# ADC_Soldier.net
KiCad netlist of a schematic drawn in Altium Designer
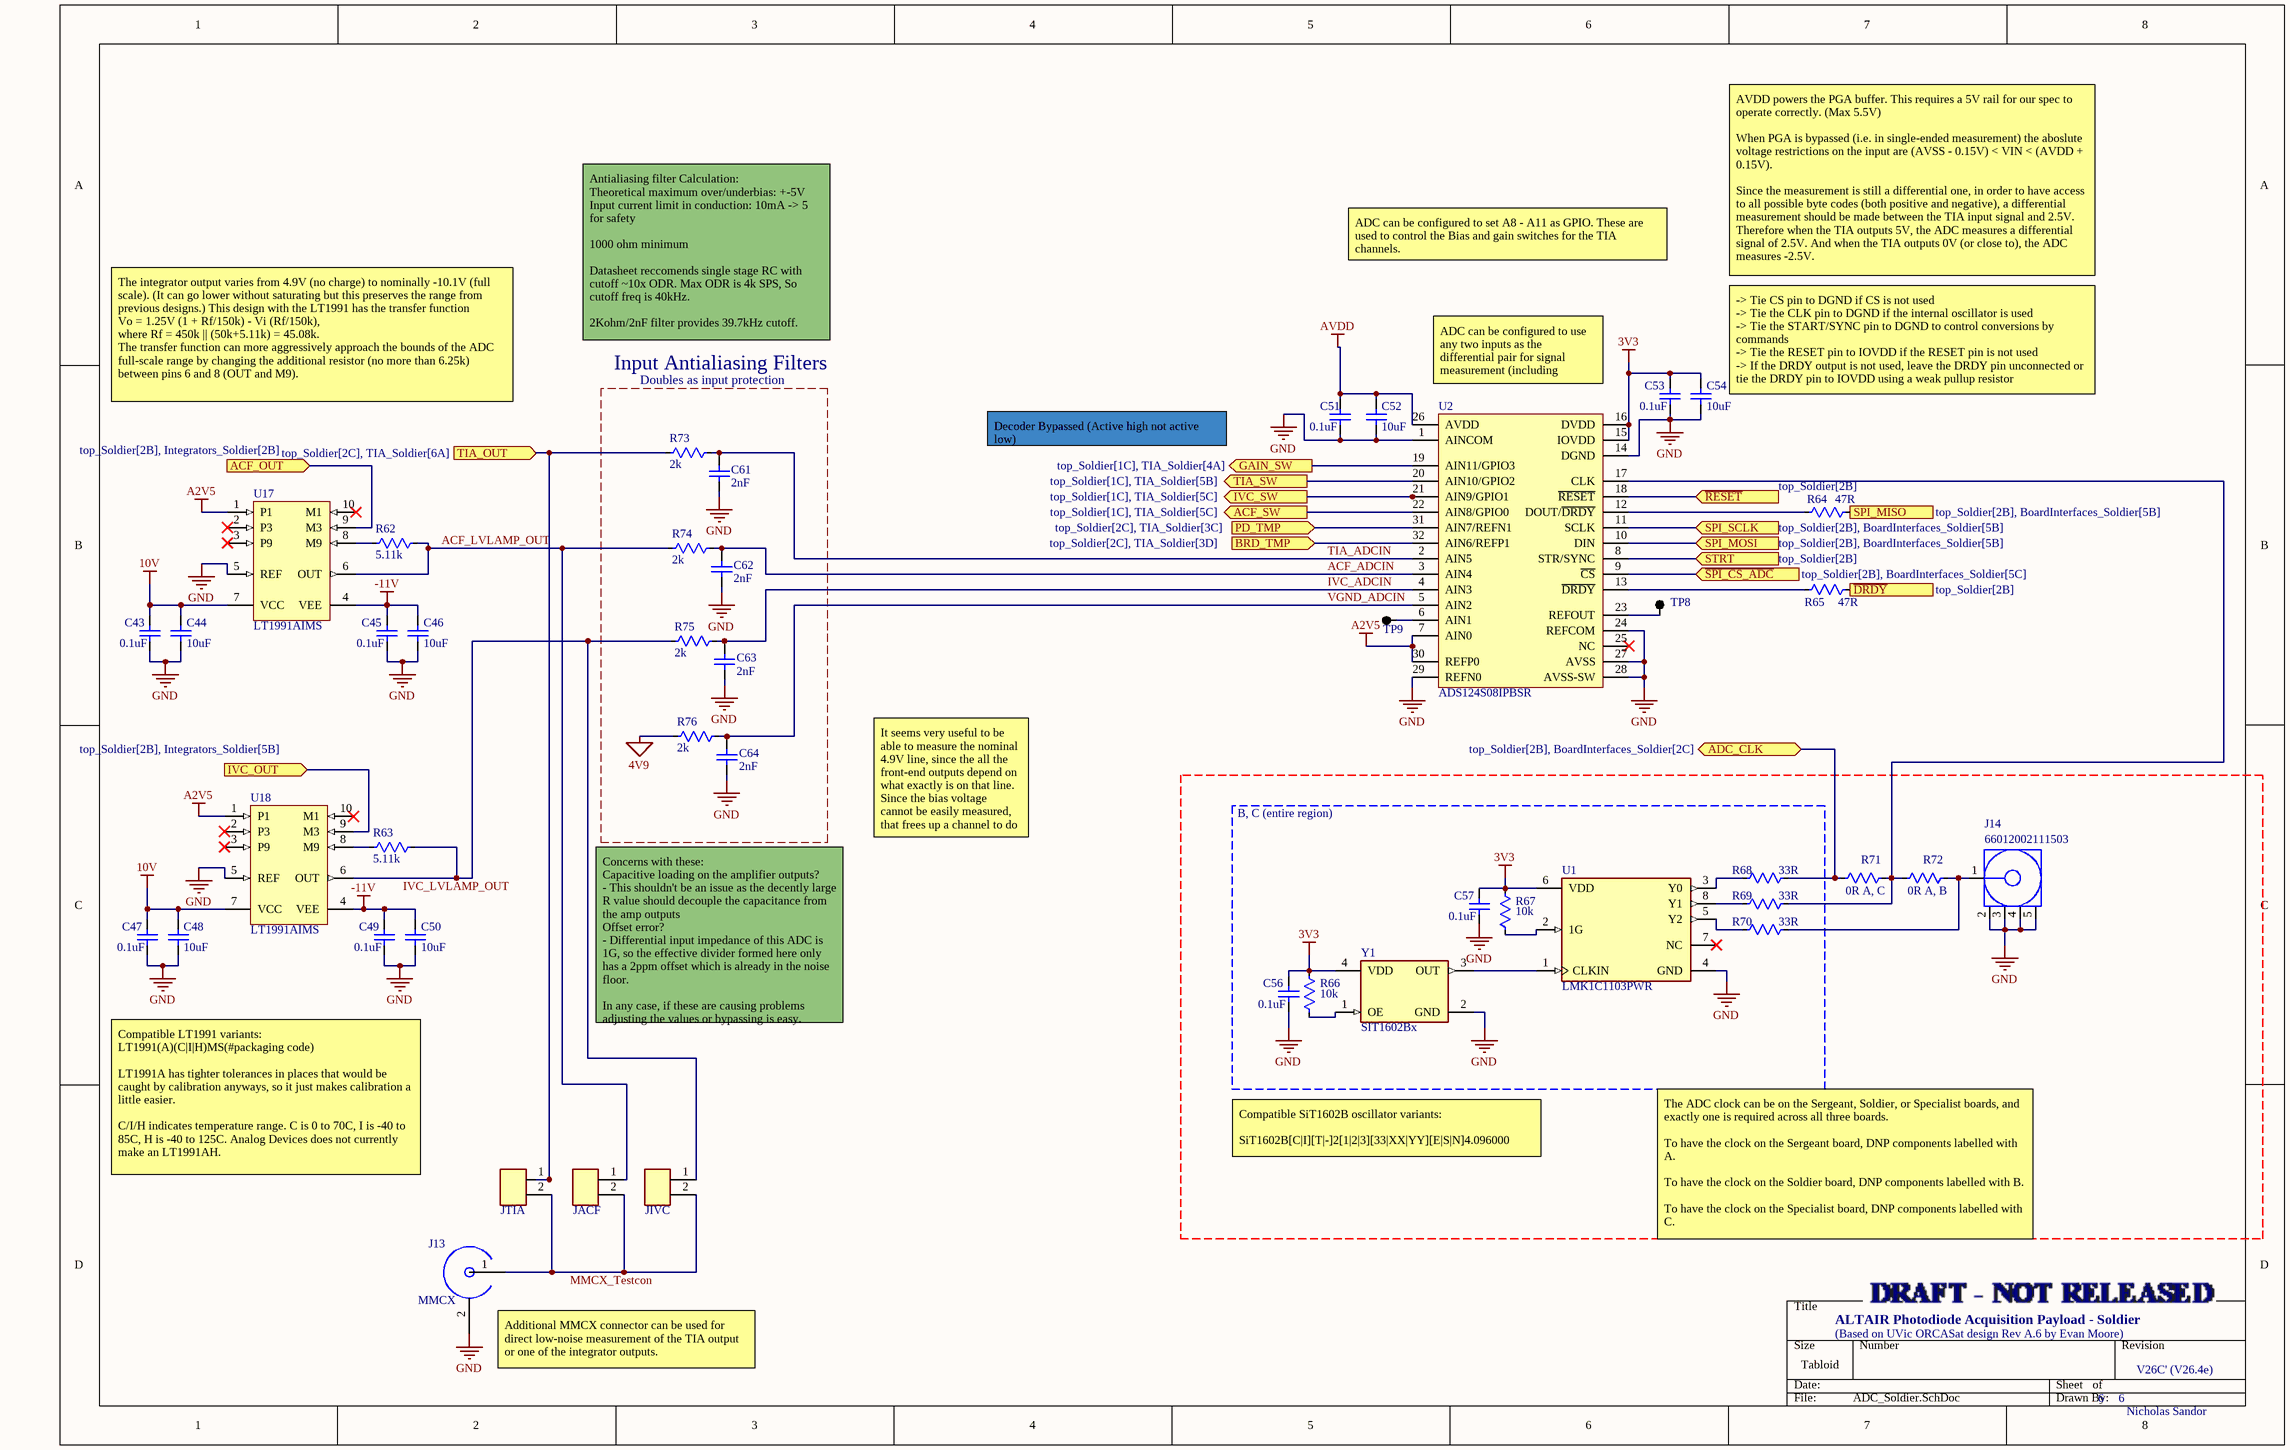
[diagram p0: ADC_Soldier.SchDoc]

(export (version "E")
  (design (tool "Eeschema 10.0.6"))
  (components
    (comp (ref "C43")
      (value "0.1uF")
      (footprint "CAP 0603 NON-IPC KEMET X7R")
      (description "Kemet C0603C104K5RACAUTO - Cap Ceramic 0.1uF 50V X7R 10% 0603 125C Paper T/R")
      (fields (field (name "MF") "Kemet") (field (name "MP") "C0603C104K5RACAUTO"))
      (libsource (lib "ALTAIR_PD_Capacitors") (part "CAP"))
    )
    (comp (ref "C44")
      (value "10uF")
      (footprint "CAP 0805 IPC MID DENSITY")
      (description "Murata GRM21BR61E106KA73L - Cap Ceramic 10uF 10% 25V X5R 0805")
      (fields (field (name "MF") "Murata") (field (name "MP") "GRM21BR61E106KA73L"))
      (libsource (lib "ALTAIR_PD_Capacitors") (part "CAP"))
    )
    (comp (ref "C45")
      (value "0.1uF")
      (footprint "CAP 0603 NON-IPC KEMET X7R")
      (description "Kemet C0603C104K5RACAUTO - Cap Ceramic 0.1uF 50V X7R 10% 0603 125C Paper T/R")
      (fields (field (name "MF") "Kemet") (field (name "MP") "C0603C104K5RACAUTO"))
      (libsource (lib "ALTAIR_PD_Capacitors") (part "CAP"))
    )
    (comp (ref "C46")
      (value "10uF")
      (footprint "CAP 0805 IPC MID DENSITY")
      (description "Murata GRM21BR61E106KA73L - Cap Ceramic 10uF 10% 25V X5R 0805")
      (fields (field (name "MF") "Murata") (field (name "MP") "GRM21BR61E106KA73L"))
      (libsource (lib "ALTAIR_PD_Capacitors") (part "CAP"))
    )
    (comp (ref "C47")
      (value "0.1uF")
      (footprint "CAP 0603 NON-IPC KEMET X7R")
      (description "Kemet C0603C104K5RACAUTO - Cap Ceramic 0.1uF 50V X7R 10% 0603 125C Paper T/R")
      (fields (field (name "MF") "Kemet") (field (name "MP") "C0603C104K5RACAUTO"))
      (libsource (lib "ALTAIR_PD_Capacitors") (part "CAP"))
    )
    (comp (ref "C48")
      (value "10uF")
      (footprint "CAP 0805 IPC MID DENSITY")
      (description "Murata GRM21BR61E106KA73L - Cap Ceramic 10uF 10% 25V X5R 0805")
      (fields (field (name "MF") "Murata") (field (name "MP") "GRM21BR61E106KA73L"))
      (libsource (lib "ALTAIR_PD_Capacitors") (part "CAP"))
    )
    (comp (ref "C49")
      (value "0.1uF")
      (footprint "CAP 0603 NON-IPC KEMET X7R")
      (description "Kemet C0603C104K5RACAUTO - Cap Ceramic 0.1uF 50V X7R 10% 0603 125C Paper T/R")
      (fields (field (name "MF") "Kemet") (field (name "MP") "C0603C104K5RACAUTO"))
      (libsource (lib "ALTAIR_PD_Capacitors") (part "CAP"))
    )
    (comp (ref "C50")
      (value "10uF")
      (footprint "CAP 0805 IPC MID DENSITY")
      (description "Murata GRM21BR61E106KA73L - Cap Ceramic 10uF 10% 25V X5R 0805")
      (fields (field (name "MF") "Murata") (field (name "MP") "GRM21BR61E106KA73L"))
      (libsource (lib "ALTAIR_PD_Capacitors") (part "CAP"))
    )
    (comp (ref "C51")
      (value "0.1uF")
      (footprint "CAP 0603 IPC MID DENSITY")
      (description "Kemet C0603C104K5RACAUTO - Cap Ceramic 0.1uF 50V X7R 10% 0603 125C Paper T/R")
      (fields (field (name "MF") "Kemet") (field (name "MP") "C0603C104K5RACAUTO"))
      (libsource (lib "ALTAIR_PD_Capacitors") (part "CAP"))
    )
    (comp (ref "C52")
      (value "10uF")
      (footprint "CAP 0805 IPC MID DENSITY")
      (description "Murata GRM21BR61E106KA73L - Cap Ceramic 10uF 10% 25V X5R 0805")
      (fields (field (name "MF") "Murata") (field (name "MP") "GRM21BR61E106KA73L"))
      (libsource (lib "ALTAIR_PD_Capacitors") (part "CAP"))
    )
    (comp (ref "C53")
      (value "0.1uF")
      (footprint "CAP 0603 IPC MID DENSITY")
      (description "Kemet C0603C104K5RACAUTO - Cap Ceramic 0.1uF 50V X7R 10% 0603 125C Paper T/R")
      (fields (field (name "MF") "Kemet") (field (name "MP") "C0603C104K5RACAUTO"))
      (libsource (lib "ALTAIR_PD_Capacitors") (part "CAP"))
    )
    (comp (ref "C54")
      (value "10uF")
      (footprint "CAP 0805 IPC MID DENSITY")
      (description "Murata GRM21BR61E106KA73L - Cap Ceramic 10uF 10% 25V X5R 0805")
      (fields (field (name "MF") "Murata") (field (name "MP") "GRM21BR61E106KA73L"))
      (libsource (lib "ALTAIR_PD_Capacitors") (part "CAP"))
    )
    (comp (ref "C56")
      (value "0.1uF")
      (footprint "CAP 0603 IPC MID DENSITY")
      (description "Kemet C0603C104K5RACAUTO - Cap Ceramic 0.1uF 50V X7R 10% 0603 125C Paper T/R")
      (fields (field (name "MF") "Kemet") (field (name "MP") "C0603C104K5RACAUTO"))
      (libsource (lib "ALTAIR_PD_Capacitors") (part "CAP"))
    )
    (comp (ref "C57")
      (value "0.1uF")
      (footprint "CAP 0603 IPC MID DENSITY")
      (description "Kemet C0603C104K5RACAUTO - Cap Ceramic 0.1uF 50V X7R 10% 0603 125C Paper T/R")
      (fields (field (name "MF") "Kemet") (field (name "MP") "C0603C104K5RACAUTO"))
      (libsource (lib "ALTAIR_PD_Capacitors") (part "CAP"))
    )
    (comp (ref "C61")
      (value "2nF")
      (footprint "CAP 0603 IPC MID DENSITY")
      (description "Cap, Nonpolar, Any, Must choose footprint manually")
      (libsource (lib "ALTAIR_PD_Capacitors") (part "CAP"))
    )
    (comp (ref "C62")
      (value "2nF")
      (footprint "CAP 0603 IPC MID DENSITY")
      (description "Cap, Nonpolar, Any, Must choose footprint manually")
      (libsource (lib "ALTAIR_PD_Capacitors") (part "CAP"))
    )
    (comp (ref "C63")
      (value "2nF")
      (footprint "CAP 0603 IPC MID DENSITY")
      (description "Cap, Nonpolar, Any, Must choose footprint manually")
      (libsource (lib "ALTAIR_PD_Capacitors") (part "CAP"))
    )
    (comp (ref "C64")
      (value "2nF")
      (footprint "CAP 0603 IPC MID DENSITY")
      (description "Cap, Nonpolar, Any, Must choose footprint manually")
      (libsource (lib "ALTAIR_PD_Capacitors") (part "CAP"))
    )
    (comp (ref "J13")
      (value "MMCX")
      (footprint "COAX MMCX SMD")
      (description "Conn MMCX F 50Ohm Solder ST SMD Gold Tray")
      (fields (field (name "MF") "Molex") (field (name "MP") "0734152061"))
      (libsource (lib "ALTAIR_PD_Coaxial") (part "MMCX_recp"))
    )
    (comp (ref "J14")
      (value "66012002111503")
      (footprint "COAX MMCX THT")
      (description "Rf Coaxial, Mmcx Jack, 50 Ohm, Pcb Rohs Compliant: Yes ¦Wurth Elektronik 66012002111503")
      (fields (field (name "MF") "Wurth Elektronik"))
      (libsource (lib "ALTAIR_PD_Coaxial") (part "CMP-207975-000001-3"))
    )
    (comp (ref "JACF")
      (value "JACF")
      (footprint "ALTAIR_PD_Headers:JUMPER 2POS 1MM PITCH THT")
      (description "2x1 Header THT 1mm Pitch")
      (fields
        (field (name "MF") "GCT (GLOBAL CONNECTOR TECHNOLOGY)")
        (field (name "MP") "BC020-02-A-0200-0300-L-G")
      )
      (libsource (lib "ALTAIR_PD_Headers") (part "BC020-02-A-0200-0300-L-G"))
    )
    (comp (ref "JIVC")
      (value "JIVC")
      (footprint "ALTAIR_PD_Headers:JUMPER 2POS 1MM PITCH THT")
      (description "2x1 Header THT 1mm Pitch")
      (fields
        (field (name "MF") "GCT (GLOBAL CONNECTOR TECHNOLOGY)")
        (field (name "MP") "BC020-02-A-0200-0300-L-G")
      )
      (libsource (lib "ALTAIR_PD_Headers") (part "BC020-02-A-0200-0300-L-G"))
    )
    (comp (ref "JTIA")
      (value "JTIA")
      (footprint "ALTAIR_PD_Headers:JUMPER 2POS 1MM PITCH THT")
      (description "2x1 Header THT 1mm Pitch")
      (fields
        (field (name "MF") "GCT (GLOBAL CONNECTOR TECHNOLOGY)")
        (field (name "MP") "BC020-02-A-0200-0300-L-G")
      )
      (libsource (lib "ALTAIR_PD_Headers") (part "BC020-02-A-0200-0300-L-G"))
    )
    (comp (ref "R62")
      (value "5.11k")
      (footprint "RES 0402 IPC MID DENSITY")
      (description "Panasonic ERA-2AEB5111X - Res 5.11k 0.1% 1/16W SMD 0402")
      (fields (field (name "MF") "Panasonic Electronic Components") (field (name "MP") "ERA-2AEB5111X"))
      (libsource (lib "ALTAIR_PD_Resistors") (part "RES"))
    )
    (comp (ref "R63")
      (value "5.11k")
      (footprint "RES 0402 IPC MID DENSITY")
      (description "Panasonic ERA-2AEB5111X - Res 5.11k 0.1% 1/16W SMD 0402")
      (fields (field (name "MF") "Panasonic Electronic Components") (field (name "MP") "ERA-2AEB5111X"))
      (libsource (lib "ALTAIR_PD_Resistors") (part "RES"))
    )
    (comp (ref "R64")
      (value "47R")
      (footprint "RES 0402 NON-IPC SEI")
      (description "Stackpole RMCF0402JT47R0 - Res 47Ohm 5% 0.063W 0402 Thick Film AEC-Q200 compliant")
      (fields (field (name "MF") "Stackpole Electronics Inc.") (field (name "MP") "RMCF0402JT47R0"))
      (libsource (lib "ALTAIR_PD_Resistors") (part "RES"))
    )
    (comp (ref "R65")
      (value "47R")
      (footprint "RES 0402 NON-IPC SEI")
      (description "Stackpole RMCF0402JT47R0 - Res 47Ohm 5% 0.063W 0402 Thick Film AEC-Q200 compliant")
      (fields (field (name "MF") "Stackpole Electronics Inc.") (field (name "MP") "RMCF0402JT47R0"))
      (libsource (lib "ALTAIR_PD_Resistors") (part "RES"))
    )
    (comp (ref "R66")
      (value "10k")
      (footprint "RES 0603 IPC MID DENSITY")
      (description "Vishay CRCW060310K0FKEA SMD 0603 10k, CRCW e3 Series, 75V, thick film, 100mW")
      (fields (field (name "MF") "Vishay Dale") (field (name "MP") "CRCW060310K0FKEA"))
      (libsource (lib "ALTAIR_PD_Resistors") (part "RES"))
    )
    (comp (ref "R67")
      (value "10k")
      (footprint "RES 0603 IPC MID DENSITY")
      (description "Vishay CRCW060310K0FKEA SMD 0603 10k, CRCW e3 Series, 75V, thick film, 100mW")
      (fields (field (name "MF") "Vishay Dale") (field (name "MP") "CRCW060310K0FKEA"))
      (libsource (lib "ALTAIR_PD_Resistors") (part "RES"))
    )
    (comp (ref "R68")
      (value "33R")
      (footprint "RES 0402 NON-IPC YAGEO")
      (description "Yageo RC0402FR-0733RL - Res 33Ohm 1% 1/16W 0402")
      (fields (field (name "MF") "YAGEO") (field (name "MP") "RC0402FR-0733RL"))
      (libsource (lib "ALTAIR_PD_Resistors") (part "RES"))
    )
    (comp (ref "R69")
      (value "33R")
      (footprint "RES 0402 NON-IPC YAGEO")
      (description "Yageo RC0402FR-0733RL - Res 33Ohm 1% 1/16W 0402")
      (fields (field (name "MF") "YAGEO") (field (name "MP") "RC0402FR-0733RL"))
      (libsource (lib "ALTAIR_PD_Resistors") (part "RES"))
    )
    (comp (ref "R70")
      (value "33R")
      (footprint "RES 0402 NON-IPC YAGEO")
      (description "Yageo RC0402FR-0733RL - Res 33Ohm 1% 1/16W 0402")
      (fields (field (name "MF") "YAGEO") (field (name "MP") "RC0402FR-0733RL"))
      (libsource (lib "ALTAIR_PD_Resistors") (part "RES"))
    )
    (comp (ref "R71")
      (value "0R A, C")
      (footprint "RES 0402 IPC MID DENSITY")
      (description "Yageo RC0402JR-070RL - Res 0 Ohms 1/16W SMD 0402")
      (fields (field (name "MF") "YAGEO") (field (name "MP") "RC0402JR-070RL"))
      (libsource (lib "ALTAIR_PD_Resistors") (part "RES"))
    )
    (comp (ref "R72")
      (value "0R A, B")
      (footprint "RES 0402 IPC MID DENSITY")
      (description "Yageo RC0402JR-070RL - Res 0 Ohms 1/16W SMD 0402")
      (fields (field (name "MF") "YAGEO") (field (name "MP") "RC0402JR-070RL"))
      (libsource (lib "ALTAIR_PD_Resistors") (part "RES"))
    )
    (comp (ref "R73")
      (value "2k")
      (footprint "RES 0603 IPC MID DENSITY")
      (description "Res, Any, Manually select footprint")
      (libsource (lib "ALTAIR_PD_Resistors") (part "RES"))
    )
    (comp (ref "R74")
      (value "2k")
      (footprint "RES 0603 IPC MID DENSITY")
      (description "Res, Any, Manually select footprint")
      (libsource (lib "ALTAIR_PD_Resistors") (part "RES"))
    )
    (comp (ref "R75")
      (value "2k")
      (footprint "RES 0603 IPC MID DENSITY")
      (description "Res, Any, Manually select footprint")
      (libsource (lib "ALTAIR_PD_Resistors") (part "RES"))
    )
    (comp (ref "R76")
      (value "2k")
      (footprint "RES 0603 IPC MID DENSITY")
      (description "Res, Any, Manually select footprint")
      (libsource (lib "ALTAIR_PD_Resistors") (part "RES"))
    )
    (comp (ref "TP8")
      (value "Testpoint")
      (footprint "TESTPOINT THT")
      (libsource (lib "ALTAIR_PD_Testpoint") (part "Testpoint"))
    )
    (comp (ref "TP9")
      (value "Testpoint")
      (footprint "TESTPOINT THT")
      (libsource (lib "ALTAIR_PD_Testpoint") (part "Testpoint"))
    )
    (comp (ref "U1")
      (value "LMK1C1103PWR")
      (footprint "8-TSSOP 0.65MM PITCH 4.4MM WIDTH IPC MID DENSITY")
      (description "LVCMOS CLOCK BUFFER 3-CHANNEL")
      (fields (field (name "MF") "Texas Instruments"))
      (libsource (lib "ALTAIR_PD_ClockParts") (part "LMK1C1103PWR"))
    )
    (comp (ref "U2")
      (value "ADS124S08IPBSR")
      (footprint "32TQFP 7X7MM IPC LOW DENSITY")
      (description "24BIT ADC Delta-Sigma 4k samples/s PGA V-reference")
      (fields (field (name "MF") "Texas Instruments"))
      (libsource (lib "ALTAIR_PD_ADCs") (part "ADS124S08IPBSR"))
    )
    (comp (ref "U17")
      (value "LT1991AIMS")
      (footprint "10-SOP 0.5MM PITCH 3MM WIDTH IPC HIGH DENSITY")
      (fields
        (field (name "MF") "Linear Technology")
        (field (name "MP") "LT1991AIMS#PBF")
        (field (name "LINEAR TECHNOLOGY PART NUMBER") "LT1991")
      )
      (libsource (lib "ALTAIR_PD_Amplifiers") (part "LT1991IMS#TRPBF"))
    )
    (comp (ref "U18")
      (value "LT1991AIMS")
      (footprint "10-SOP 0.5MM PITCH 3MM WIDTH IPC HIGH DENSITY")
      (fields
        (field (name "MF") "Linear Technology")
        (field (name "MP") "LT1991AIMS#PBF")
        (field (name "LINEAR TECHNOLOGY PART NUMBER") "LT1991")
      )
      (libsource (lib "ALTAIR_PD_Amplifiers") (part "LT1991IMS#TRPBF"))
    )
    (comp (ref "Y1")
      (value "SIT1602Bx")
      (footprint "4PQFN NON-IPC SITIME")
      (description "MEMS OSC XO 4.096MHZ H/LVCMOS")
      (fields (field (name "MF") "SiTime") (field (name "MP") "SiT1602BC-21-XXN-4.096000"))
      (libsource (lib "ALTAIR_PD_ClockParts") (part "SIT1602Bx"))
    )
  )
  (nets
    (net (code "1") (name "-11V") (class "Default")
      (node (ref "C45") (pin "2") (pinfunction "2_2") (pintype "passive"))
      (node (ref "C46") (pin "2") (pinfunction "2_2") (pintype "passive"))
      (node (ref "C49") (pin "2") (pinfunction "2_2") (pintype "passive"))
      (node (ref "C50") (pin "2") (pinfunction "2_2") (pintype "passive"))
      (node (ref "U17") (pin "4") (pinfunction "VEE_4") (pintype "power_in"))
      (node (ref "U18") (pin "4") (pinfunction "VEE_4") (pintype "power_in"))
    )
    (net (code "2") (name "/ACF_ADCIN") (class "Default")
      (node (ref "C62") (pin "2") (pinfunction "2_2") (pintype "passive"))
      (node (ref "R74") (pin "2") (pinfunction "2_2") (pintype "passive"))
      (node (ref "U2") (pin "3") (pinfunction "AIN4_3") (pintype "passive"))
    )
    (net (code "3") (name "/ACF_LVLAMP_OUT") (class "Default")
      (node (ref "JACF") (pin "1") (pinfunction "1_1") (pintype "passive"))
      (node (ref "R62") (pin "2") (pinfunction "2_2") (pintype "passive"))
      (node (ref "R74") (pin "1") (pinfunction "1_1") (pintype "passive"))
      (node (ref "U17") (pin "6") (pinfunction "OUT_6") (pintype "output"))
    )
    (net (code "4") (name "/ACF_OUT") (class "Default")
      (node (ref "U17") (pin "9") (pinfunction "M3_9") (pintype "input"))
    )
    (net (code "5") (name "/ACF_SW") (class "Default")
      (node (ref "U2") (pin "22") (pinfunction "AIN8/GPIO0_22") (pintype "passive"))
    )
    (net (code "6") (name "/ADC_CLK") (class "Default")
      (node (ref "R68") (pin "1") (pinfunction "1_1") (pintype "passive"))
      (node (ref "R71") (pin "2") (pinfunction "2_2") (pintype "passive"))
    )
    (net (code "7") (name "/BRD_TMP") (class "Default")
      (node (ref "U2") (pin "32") (pinfunction "AIN6/REFP1_32") (pintype "passive"))
    )
    (net (code "8") (name "/DRDY") (class "Default")
      (node (ref "R65") (pin "2") (pinfunction "2_2") (pintype "passive"))
    )
    (net (code "9") (name "/GAIN_SW") (class "Default")
      (node (ref "U2") (pin "19") (pinfunction "AIN11/GPIO3_19") (pintype "passive"))
    )
    (net (code "10") (name "/IVC_ADCIN") (class "Default")
      (node (ref "C63") (pin "2") (pinfunction "2_2") (pintype "passive"))
      (node (ref "R75") (pin "2") (pinfunction "2_2") (pintype "passive"))
      (node (ref "U2") (pin "4") (pinfunction "AIN3_4") (pintype "passive"))
    )
    (net (code "11") (name "/IVC_LVLAMP_OUT") (class "Default")
      (node (ref "JIVC") (pin "1") (pinfunction "1_1") (pintype "passive"))
      (node (ref "R63") (pin "2") (pinfunction "2_2") (pintype "passive"))
      (node (ref "R75") (pin "1") (pinfunction "1_1") (pintype "passive"))
      (node (ref "U18") (pin "6") (pinfunction "OUT_6") (pintype "output"))
    )
    (net (code "12") (name "/IVC_OUT") (class "Default")
      (node (ref "U18") (pin "9") (pinfunction "M3_9") (pintype "input"))
    )
    (net (code "13") (name "/IVC_SW") (class "Default")
      (node (ref "U2") (pin "21") (pinfunction "AIN9/GPIO1_21") (pintype "passive"))
    )
    (net (code "14") (name "/MMCX_Testcon") (class "Default")
      (node (ref "J13") (pin "1") (pinfunction "1_1") (pintype "passive"))
      (node (ref "JACF") (pin "2") (pinfunction "2_2") (pintype "passive"))
      (node (ref "JIVC") (pin "2") (pinfunction "2_2") (pintype "passive"))
      (node (ref "JTIA") (pin "2") (pinfunction "2_2") (pintype "passive"))
    )
    (net (code "15") (name "/PD_TMP") (class "Default")
      (node (ref "U2") (pin "31") (pinfunction "AIN7/REFN1_31") (pintype "passive"))
    )
    (net (code "16") (name "/RESET") (class "Default")
      (node (ref "U2") (pin "18") (pinfunction "~{RESET}_18") (pintype "passive"))
    )
    (net (code "17") (name "/SPI_CS_ADC") (class "Default")
      (node (ref "U2") (pin "9") (pinfunction "~{CS}_9") (pintype "passive"))
    )
    (net (code "18") (name "/SPI_MISO") (class "Default")
      (node (ref "R64") (pin "2") (pinfunction "2_2") (pintype "passive"))
    )
    (net (code "19") (name "/SPI_MOSI") (class "Default")
      (node (ref "U2") (pin "10") (pinfunction "DIN_10") (pintype "passive"))
    )
    (net (code "20") (name "/SPI_SCLK") (class "Default")
      (node (ref "U2") (pin "11") (pinfunction "SCLK_11") (pintype "passive"))
    )
    (net (code "21") (name "/STRT") (class "Default")
      (node (ref "U2") (pin "8") (pinfunction "STR/SYNC_8") (pintype "passive"))
    )
    (net (code "22") (name "/TIA_ADCIN") (class "Default")
      (node (ref "C61") (pin "2") (pinfunction "2_2") (pintype "passive"))
      (node (ref "R73") (pin "2") (pinfunction "2_2") (pintype "passive"))
      (node (ref "U2") (pin "2") (pinfunction "AIN5_2") (pintype "passive"))
    )
    (net (code "23") (name "/TIA_OUT") (class "Default")
      (node (ref "JTIA") (pin "1") (pinfunction "1_1") (pintype "passive"))
      (node (ref "R73") (pin "1") (pinfunction "1_1") (pintype "passive"))
    )
    (net (code "24") (name "/TIA_SW") (class "Default")
      (node (ref "U2") (pin "20") (pinfunction "AIN10/GPIO2_20") (pintype "passive"))
    )
    (net (code "25") (name "/VGND_ADCIN") (class "Default")
      (node (ref "C64") (pin "2") (pinfunction "2_2") (pintype "passive"))
      (node (ref "R76") (pin "2") (pinfunction "2_2") (pintype "passive"))
      (node (ref "U2") (pin "5") (pinfunction "AIN2_5") (pintype "passive"))
    )
    (net (code "26") (name "3V3") (class "Default")
      (node (ref "C53") (pin "2") (pinfunction "2_2") (pintype "passive"))
      (node (ref "C54") (pin "2") (pinfunction "2_2") (pintype "passive"))
      (node (ref "C56") (pin "2") (pinfunction "2_2") (pintype "passive"))
      (node (ref "C57") (pin "2") (pinfunction "2_2") (pintype "passive"))
      (node (ref "R66") (pin "2") (pinfunction "2_2") (pintype "passive"))
      (node (ref "R67") (pin "2") (pinfunction "2_2") (pintype "passive"))
      (node (ref "U1") (pin "6") (pinfunction "VDD_6") (pintype "power_in"))
      (node (ref "U2") (pin "15") (pinfunction "IOVDD_15") (pintype "passive"))
      (node (ref "U2") (pin "16") (pinfunction "DVDD_16") (pintype "passive"))
      (node (ref "Y1") (pin "4") (pinfunction "VDD_4") (pintype "power_in"))
    )
    (net (code "27") (name "4V9") (class "Default")
      (node (ref "R76") (pin "1") (pinfunction "1_1") (pintype "passive"))
    )
    (net (code "28") (name "10V") (class "Default")
      (node (ref "C43") (pin "2") (pinfunction "2_2") (pintype "passive"))
      (node (ref "C44") (pin "2") (pinfunction "2_2") (pintype "passive"))
      (node (ref "C47") (pin "2") (pinfunction "2_2") (pintype "passive"))
      (node (ref "C48") (pin "2") (pinfunction "2_2") (pintype "passive"))
      (node (ref "U17") (pin "7") (pinfunction "VCC_7") (pintype "power_in"))
      (node (ref "U18") (pin "7") (pinfunction "VCC_7") (pintype "power_in"))
    )
    (net (code "29") (name "A2V5") (class "Default")
      (node (ref "U17") (pin "1") (pinfunction "P1_1") (pintype "input"))
      (node (ref "U18") (pin "1") (pinfunction "P1_1") (pintype "input"))
      (node (ref "U2") (pin "30") (pinfunction "REFP0_30") (pintype "passive"))
      (node (ref "U2") (pin "7") (pinfunction "AIN0_7") (pintype "passive"))
    )
    (net (code "30") (name "AVDD") (class "Default")
      (node (ref "C51") (pin "2") (pinfunction "2_2") (pintype "passive"))
      (node (ref "C52") (pin "2") (pinfunction "2_2") (pintype "passive"))
      (node (ref "U2") (pin "26") (pinfunction "AVDD_26") (pintype "passive"))
    )
    (net (code "31") (name "GND") (class "Default")
      (node (ref "C43") (pin "1") (pinfunction "1_1") (pintype "passive"))
      (node (ref "C44") (pin "1") (pinfunction "1_1") (pintype "passive"))
      (node (ref "C45") (pin "1") (pinfunction "1_1") (pintype "passive"))
      (node (ref "C46") (pin "1") (pinfunction "1_1") (pintype "passive"))
      (node (ref "C47") (pin "1") (pinfunction "1_1") (pintype "passive"))
      (node (ref "C48") (pin "1") (pinfunction "1_1") (pintype "passive"))
      (node (ref "C49") (pin "1") (pinfunction "1_1") (pintype "passive"))
      (node (ref "C50") (pin "1") (pinfunction "1_1") (pintype "passive"))
      (node (ref "C51") (pin "1") (pinfunction "1_1") (pintype "passive"))
      (node (ref "C52") (pin "1") (pinfunction "1_1") (pintype "passive"))
      (node (ref "C53") (pin "1") (pinfunction "1_1") (pintype "passive"))
      (node (ref "C54") (pin "1") (pinfunction "1_1") (pintype "passive"))
      (node (ref "C56") (pin "1") (pinfunction "1_1") (pintype "passive"))
      (node (ref "C57") (pin "1") (pinfunction "1_1") (pintype "passive"))
      (node (ref "C61") (pin "1") (pinfunction "1_1") (pintype "passive"))
      (node (ref "C62") (pin "1") (pinfunction "1_1") (pintype "passive"))
      (node (ref "C63") (pin "1") (pinfunction "1_1") (pintype "passive"))
      (node (ref "C64") (pin "1") (pinfunction "1_1") (pintype "passive"))
      (node (ref "J13") (pin "2") (pinfunction "2_2") (pintype "passive"))
      (node (ref "J14") (pin "2") (pinfunction "GND_2") (pintype "passive"))
      (node (ref "J14") (pin "3") (pinfunction "GND_3") (pintype "passive"))
      (node (ref "J14") (pin "4") (pinfunction "GND_4") (pintype "passive"))
      (node (ref "J14") (pin "5") (pinfunction "GND_5") (pintype "passive"))
      (node (ref "U1") (pin "4") (pinfunction "GND_4") (pintype "power_in"))
      (node (ref "U17") (pin "5") (pinfunction "REF_5") (pintype "input"))
      (node (ref "U18") (pin "5") (pinfunction "REF_5") (pintype "input"))
      (node (ref "U2") (pin "1") (pinfunction "AINCOM_1") (pintype "passive"))
      (node (ref "U2") (pin "14") (pinfunction "DGND_14") (pintype "passive"))
      (node (ref "U2") (pin "24") (pinfunction "REFCOM_24") (pintype "passive"))
      (node (ref "U2") (pin "27") (pinfunction "AVSS_27") (pintype "passive"))
      (node (ref "U2") (pin "28") (pinfunction "AVSS-SW_28") (pintype "passive"))
      (node (ref "U2") (pin "29") (pinfunction "REFN0_29") (pintype "passive"))
      (node (ref "Y1") (pin "2") (pinfunction "GND_2") (pintype "power_in"))
    )
    (net (code "32") (name "Net-(J14-Signal)") (class "Default")
      (node (ref "J14") (pin "1") (pinfunction "Signal_1") (pintype "passive"))
      (node (ref "R70") (pin "1") (pinfunction "1_1") (pintype "passive"))
      (node (ref "R72") (pin "1") (pinfunction "1_1") (pintype "passive"))
    )
    (net (code "33") (name "Net-(U1-1G)") (class "Default")
      (node (ref "R67") (pin "1") (pinfunction "1_1") (pintype "passive"))
      (node (ref "U1") (pin "2") (pinfunction "1G_2") (pintype "input"))
    )
    (net (code "34") (name "Net-(U1-CLKIN)") (class "Default")
      (node (ref "U1") (pin "1") (pinfunction "CLKIN_1") (pintype "input"))
      (node (ref "Y1") (pin "3") (pinfunction "OUT_3") (pintype "output"))
    )
    (net (code "35") (name "Net-(U1-Y0)") (class "Default")
      (node (ref "R68") (pin "2") (pinfunction "2_2") (pintype "passive"))
      (node (ref "U1") (pin "3") (pinfunction "Y0_3") (pintype "output"))
    )
    (net (code "36") (name "Net-(U1-Y1)") (class "Default")
      (node (ref "R69") (pin "2") (pinfunction "2_2") (pintype "passive"))
      (node (ref "U1") (pin "8") (pinfunction "Y1_8") (pintype "output"))
    )
    (net (code "37") (name "Net-(U1-Y2)") (class "Default")
      (node (ref "R70") (pin "2") (pinfunction "2_2") (pintype "passive"))
      (node (ref "U1") (pin "5") (pinfunction "Y2_5") (pintype "output"))
    )
    (net (code "38") (name "Net-(U2-AIN1)") (class "Default")
      (node (ref "TP9") (pin "1") (pinfunction "1_1") (pintype "passive"))
      (node (ref "U2") (pin "6") (pinfunction "AIN1_6") (pintype "passive"))
    )
    (net (code "39") (name "Net-(U2-CLK)") (class "Default")
      (node (ref "R69") (pin "1") (pinfunction "1_1") (pintype "passive"))
      (node (ref "R71") (pin "1") (pinfunction "1_1") (pintype "passive"))
      (node (ref "R72") (pin "2") (pinfunction "2_2") (pintype "passive"))
      (node (ref "U2") (pin "17") (pinfunction "CLK_17") (pintype "passive"))
    )
    (net (code "40") (name "Net-(U2-DOUT{slash}~{DRDY})") (class "Default")
      (node (ref "R64") (pin "1") (pinfunction "1_1") (pintype "passive"))
      (node (ref "U2") (pin "12") (pinfunction "DOUT/~{DRDY}_12") (pintype "passive"))
    )
    (net (code "41") (name "Net-(U2-REFOUT)") (class "Default")
      (node (ref "TP8") (pin "1") (pinfunction "1_1") (pintype "passive"))
      (node (ref "U2") (pin "23") (pinfunction "REFOUT_23") (pintype "passive"))
    )
    (net (code "42") (name "Net-(U2-~{DRDY})") (class "Default")
      (node (ref "R65") (pin "1") (pinfunction "1_1") (pintype "passive"))
      (node (ref "U2") (pin "13") (pinfunction "~{DRDY}_13") (pintype "passive"))
    )
    (net (code "43") (name "Net-(U17-M9)") (class "Default")
      (node (ref "R62") (pin "1") (pinfunction "1_1") (pintype "passive"))
      (node (ref "U17") (pin "8") (pinfunction "M9_8") (pintype "input"))
    )
    (net (code "44") (name "Net-(U18-M9)") (class "Default")
      (node (ref "R63") (pin "1") (pinfunction "1_1") (pintype "passive"))
      (node (ref "U18") (pin "8") (pinfunction "M9_8") (pintype "input"))
    )
    (net (code "45") (name "Net-(Y1-OE)") (class "Default")
      (node (ref "R66") (pin "1") (pinfunction "1_1") (pintype "passive"))
      (node (ref "Y1") (pin "1") (pinfunction "OE_1") (pintype "input"))
    )
    (net (code "46") (name "unconnected-(U1-NC-Pad7)") (class "Default")
      (node (ref "U1") (pin "7") (pinfunction "NC_7") (pintype "passive+no_connect"))
    )
    (net (code "47") (name "unconnected-(U2-NC-Pad25)") (class "Default")
      (node (ref "U2") (pin "25") (pinfunction "NC_25") (pintype "passive+no_connect"))
    )
    (net (code "48") (name "unconnected-(U17-M1-Pad10)") (class "Default")
      (node (ref "U17") (pin "10") (pinfunction "M1_10") (pintype "input+no_connect"))
    )
    (net (code "49") (name "unconnected-(U17-P3-Pad2)") (class "Default")
      (node (ref "U17") (pin "2") (pinfunction "P3_2") (pintype "input+no_connect"))
    )
    (net (code "50") (name "unconnected-(U17-P9-Pad3)") (class "Default")
      (node (ref "U17") (pin "3") (pinfunction "P9_3") (pintype "input+no_connect"))
    )
    (net (code "51") (name "unconnected-(U18-M1-Pad10)") (class "Default")
      (node (ref "U18") (pin "10") (pinfunction "M1_10") (pintype "input+no_connect"))
    )
    (net (code "52") (name "unconnected-(U18-P3-Pad2)") (class "Default")
      (node (ref "U18") (pin "2") (pinfunction "P3_2") (pintype "input+no_connect"))
    )
    (net (code "53") (name "unconnected-(U18-P9-Pad3)") (class "Default")
      (node (ref "U18") (pin "3") (pinfunction "P9_3") (pintype "input+no_connect"))
    )
  )
)
